# breakout_32QFN-32TQFP.net
KiCad netlist of a schematic drawn in Altium Designer
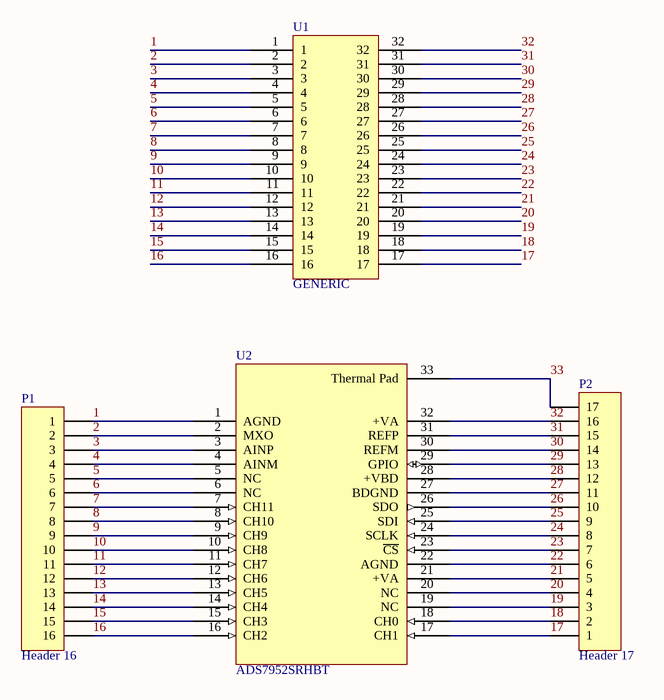
[diagram p0: breakout_32QFN-32TQFP.SchDoc]

(export (version "E")
  (design (tool "Eeschema 10.0.6"))
  (components
    (comp (ref "P1")
      (value "Header 16")
      (footprint "HDR1X16")
      (description "Header, 16-Pin")
      (fields (field (name "PUBLISHER") "Altium Limited"))
      (libsource (lib "Miscellaneous Connectors") (part "Header 16"))
    )
    (comp (ref "P2")
      (value "Header 17")
      (footprint "HDR1X17")
      (description "Header, 17-Pin")
      (fields (field (name "PUBLISHER") "Altium Limited"))
      (libsource (lib "Miscellaneous Connectors") (part "Header 17"))
    )
    (comp (ref "U1")
      (value "GENERIC")
      (footprint "TQFP80P900X900X120-32N-GENERIC")
      (libsource (lib "Generic-32TQFP") (part "TQFP80P900X900X120-32N-GENERIC"))
    )
    (comp (ref "U2")
      (value "ADS7952SRHBT")
      (footprint "ADS7952SRHBT")
      (description "Digikey: 296-25843-1-ND -- 12 Bit Analog to Digital Converter 12 Input 1 SAR 32-VQFN (5x5)")
      (libsource (lib "TexasInstruments_ADS7952SRHBT") (part "ADS7952SRHBT"))
    )
  )
  (nets
    (net (code "1") (name "/1") (class "Default")
      (node (ref "P1") (pin "1") (pinfunction "1_1") (pintype "passive"))
      (node (ref "U1") (pin "1") (pinfunction "1_1") (pintype "passive"))
      (node (ref "U2") (pin "1") (pinfunction "AGND_1") (pintype "passive"))
    )
    (net (code "2") (name "/2") (class "Default")
      (node (ref "P1") (pin "2") (pinfunction "2_2") (pintype "passive"))
      (node (ref "U1") (pin "2") (pinfunction "2_2") (pintype "passive"))
      (node (ref "U2") (pin "2") (pinfunction "MXO_2") (pintype "passive"))
    )
    (net (code "3") (name "/3") (class "Default")
      (node (ref "P1") (pin "3") (pinfunction "3_3") (pintype "passive"))
      (node (ref "U1") (pin "3") (pinfunction "3_3") (pintype "passive"))
      (node (ref "U2") (pin "3") (pinfunction "AINP_3") (pintype "passive"))
    )
    (net (code "4") (name "/4") (class "Default")
      (node (ref "P1") (pin "4") (pinfunction "4_4") (pintype "passive"))
      (node (ref "U1") (pin "4") (pinfunction "4_4") (pintype "passive"))
      (node (ref "U2") (pin "4") (pinfunction "AINM_4") (pintype "passive"))
    )
    (net (code "5") (name "/5") (class "Default")
      (node (ref "P1") (pin "5") (pinfunction "5_5") (pintype "passive"))
      (node (ref "U1") (pin "5") (pinfunction "5_5") (pintype "passive"))
      (node (ref "U2") (pin "5") (pinfunction "NC_5") (pintype "passive"))
    )
    (net (code "6") (name "/6") (class "Default")
      (node (ref "P1") (pin "6") (pinfunction "6_6") (pintype "passive"))
      (node (ref "U1") (pin "6") (pinfunction "6_6") (pintype "passive"))
      (node (ref "U2") (pin "6") (pinfunction "NC_6") (pintype "tri_state"))
    )
    (net (code "7") (name "/7") (class "Default")
      (node (ref "P1") (pin "7") (pinfunction "7_7") (pintype "passive"))
      (node (ref "U1") (pin "7") (pinfunction "7_7") (pintype "passive"))
      (node (ref "U2") (pin "7") (pinfunction "CH11_7") (pintype "input"))
    )
    (net (code "8") (name "/8") (class "Default")
      (node (ref "P1") (pin "8") (pinfunction "8_8") (pintype "passive"))
      (node (ref "U1") (pin "8") (pinfunction "8_8") (pintype "passive"))
      (node (ref "U2") (pin "8") (pinfunction "CH10_8") (pintype "input"))
    )
    (net (code "9") (name "/9") (class "Default")
      (node (ref "P1") (pin "9") (pinfunction "9_9") (pintype "passive"))
      (node (ref "U1") (pin "9") (pinfunction "9_9") (pintype "passive"))
      (node (ref "U2") (pin "9") (pinfunction "CH9_9") (pintype "input"))
    )
    (net (code "10") (name "/10") (class "Default")
      (node (ref "P1") (pin "10") (pinfunction "10_10") (pintype "passive"))
      (node (ref "U1") (pin "10") (pinfunction "10_10") (pintype "passive"))
      (node (ref "U2") (pin "10") (pinfunction "CH8_10") (pintype "input"))
    )
    (net (code "11") (name "/11") (class "Default")
      (node (ref "P1") (pin "11") (pinfunction "11_11") (pintype "passive"))
      (node (ref "U1") (pin "11") (pinfunction "11_11") (pintype "passive"))
      (node (ref "U2") (pin "11") (pinfunction "CH7_11") (pintype "input"))
    )
    (net (code "12") (name "/12") (class "Default")
      (node (ref "P1") (pin "12") (pinfunction "12_12") (pintype "passive"))
      (node (ref "U1") (pin "12") (pinfunction "12_12") (pintype "passive"))
      (node (ref "U2") (pin "12") (pinfunction "CH6_12") (pintype "input"))
    )
    (net (code "13") (name "/13") (class "Default")
      (node (ref "P1") (pin "13") (pinfunction "13_13") (pintype "passive"))
      (node (ref "U1") (pin "13") (pinfunction "13_13") (pintype "passive"))
      (node (ref "U2") (pin "13") (pinfunction "CH5_13") (pintype "input"))
    )
    (net (code "14") (name "/14") (class "Default")
      (node (ref "P1") (pin "14") (pinfunction "14_14") (pintype "passive"))
      (node (ref "U1") (pin "14") (pinfunction "14_14") (pintype "passive"))
      (node (ref "U2") (pin "14") (pinfunction "CH4_14") (pintype "input"))
    )
    (net (code "15") (name "/15") (class "Default")
      (node (ref "P1") (pin "15") (pinfunction "15_15") (pintype "passive"))
      (node (ref "U1") (pin "15") (pinfunction "15_15") (pintype "passive"))
      (node (ref "U2") (pin "15") (pinfunction "CH3_15") (pintype "input"))
    )
    (net (code "16") (name "/16") (class "Default")
      (node (ref "P1") (pin "16") (pinfunction "16_16") (pintype "passive"))
      (node (ref "U1") (pin "16") (pinfunction "16_16") (pintype "passive"))
      (node (ref "U2") (pin "16") (pinfunction "CH2_16") (pintype "input"))
    )
    (net (code "17") (name "/17") (class "Default")
      (node (ref "P2") (pin "1") (pinfunction "1_1") (pintype "passive"))
      (node (ref "U1") (pin "17") (pinfunction "17_17") (pintype "passive"))
      (node (ref "U2") (pin "17") (pinfunction "CH1_17") (pintype "input"))
    )
    (net (code "18") (name "/18") (class "Default")
      (node (ref "P2") (pin "2") (pinfunction "2_2") (pintype "passive"))
      (node (ref "U1") (pin "18") (pinfunction "18_18") (pintype "passive"))
      (node (ref "U2") (pin "18") (pinfunction "CH0_18") (pintype "input"))
    )
    (net (code "19") (name "/19") (class "Default")
      (node (ref "P2") (pin "3") (pinfunction "3_3") (pintype "passive"))
      (node (ref "U1") (pin "19") (pinfunction "19_19") (pintype "passive"))
      (node (ref "U2") (pin "19") (pinfunction "NC_19") (pintype "tri_state"))
    )
    (net (code "20") (name "/20") (class "Default")
      (node (ref "P2") (pin "4") (pinfunction "4_4") (pintype "passive"))
      (node (ref "U1") (pin "20") (pinfunction "20_20") (pintype "passive"))
      (node (ref "U2") (pin "20") (pinfunction "NC_20") (pintype "tri_state"))
    )
    (net (code "21") (name "/21") (class "Default")
      (node (ref "P2") (pin "5") (pinfunction "5_5") (pintype "passive"))
      (node (ref "U1") (pin "21") (pinfunction "21_21") (pintype "passive"))
      (node (ref "U2") (pin "21") (pinfunction "+VA_21") (pintype "passive"))
    )
    (net (code "22") (name "/22") (class "Default")
      (node (ref "P2") (pin "6") (pinfunction "6_6") (pintype "passive"))
      (node (ref "U1") (pin "22") (pinfunction "22_22") (pintype "passive"))
      (node (ref "U2") (pin "22") (pinfunction "AGND_22") (pintype "passive"))
    )
    (net (code "23") (name "/23") (class "Default")
      (node (ref "P2") (pin "7") (pinfunction "7_7") (pintype "passive"))
      (node (ref "U1") (pin "23") (pinfunction "23_23") (pintype "passive"))
      (node (ref "U2") (pin "23") (pinfunction "~{CS}_23") (pintype "input"))
    )
    (net (code "24") (name "/24") (class "Default")
      (node (ref "P2") (pin "8") (pinfunction "8_8") (pintype "passive"))
      (node (ref "U1") (pin "24") (pinfunction "24_24") (pintype "passive"))
      (node (ref "U2") (pin "24") (pinfunction "SCLK_24") (pintype "input"))
    )
    (net (code "25") (name "/25") (class "Default")
      (node (ref "P2") (pin "9") (pinfunction "9_9") (pintype "passive"))
      (node (ref "U1") (pin "25") (pinfunction "25_25") (pintype "passive"))
      (node (ref "U2") (pin "25") (pinfunction "SDI_25") (pintype "input"))
    )
    (net (code "26") (name "/26") (class "Default")
      (node (ref "P2") (pin "10") (pinfunction "10_10") (pintype "passive"))
      (node (ref "U1") (pin "26") (pinfunction "26_26") (pintype "passive"))
      (node (ref "U2") (pin "26") (pinfunction "SDO_26") (pintype "output"))
    )
    (net (code "27") (name "/27") (class "Default")
      (node (ref "P2") (pin "11") (pinfunction "11_11") (pintype "passive"))
      (node (ref "U1") (pin "27") (pinfunction "27_27") (pintype "passive"))
      (node (ref "U2") (pin "27") (pinfunction "BDGND_27") (pintype "passive"))
    )
    (net (code "28") (name "/28") (class "Default")
      (node (ref "P2") (pin "12") (pinfunction "12_12") (pintype "passive"))
      (node (ref "U1") (pin "28") (pinfunction "28_28") (pintype "passive"))
      (node (ref "U2") (pin "28") (pinfunction "+VBD_28") (pintype "passive"))
    )
    (net (code "29") (name "/29") (class "Default")
      (node (ref "P2") (pin "13") (pinfunction "13_13") (pintype "passive"))
      (node (ref "U1") (pin "29") (pinfunction "29_29") (pintype "passive"))
      (node (ref "U2") (pin "29") (pinfunction "GPIO_29") (pintype "bidirectional"))
    )
    (net (code "30") (name "/30") (class "Default")
      (node (ref "P2") (pin "14") (pinfunction "14_14") (pintype "passive"))
      (node (ref "U1") (pin "30") (pinfunction "30_30") (pintype "passive"))
      (node (ref "U2") (pin "30") (pinfunction "REFM_30") (pintype "passive"))
    )
    (net (code "31") (name "/31") (class "Default")
      (node (ref "P2") (pin "15") (pinfunction "15_15") (pintype "passive"))
      (node (ref "U1") (pin "31") (pinfunction "31_31") (pintype "passive"))
      (node (ref "U2") (pin "31") (pinfunction "REFP_31") (pintype "passive"))
    )
    (net (code "32") (name "/32") (class "Default")
      (node (ref "P2") (pin "16") (pinfunction "16_16") (pintype "passive"))
      (node (ref "U1") (pin "32") (pinfunction "32_32") (pintype "passive"))
      (node (ref "U2") (pin "32") (pinfunction "+VA_32") (pintype "passive"))
    )
    (net (code "33") (name "/33") (class "Default")
      (node (ref "P2") (pin "17") (pinfunction "17_17") (pintype "passive"))
      (node (ref "U2") (pin "33") (pinfunction "Thermal_Pad_33") (pintype "passive"))
    )
  )
)
